# Cell_monitoring_and_balancing.net
KiCad netlist of a schematic drawn in Altium Designer
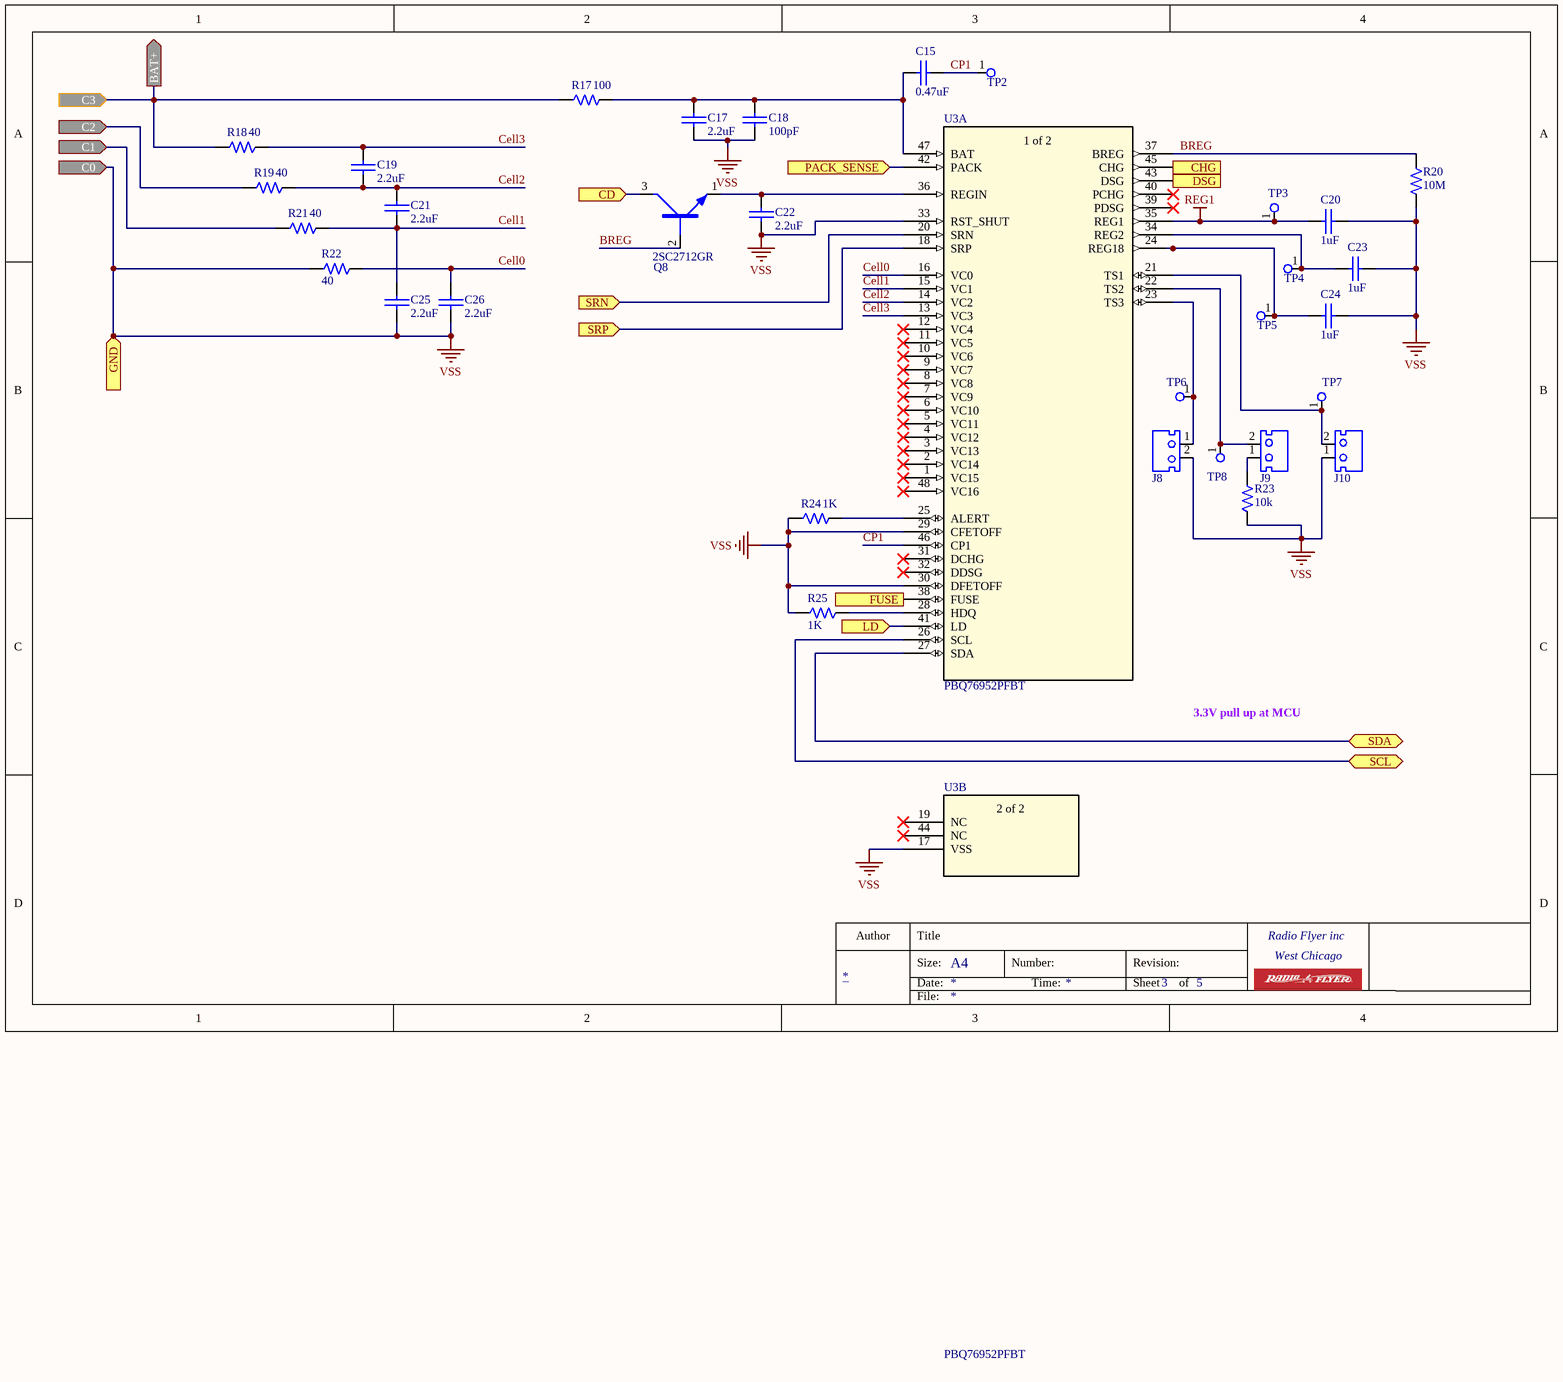
[diagram p0: Cell monitoring and balancing.SchDoc]

(export (version "E")
  (design (tool "Eeschema 10.0.6"))
  (components
    (comp (ref "C15")
      (value "0.47uF")
      (footprint "CAPC0603-RW")
      (description "CAP X7R .01UF 16V +-10% 0603 WALSIN L")
      (fields
        (field (name "MFG") "WALSIN")
        (field (name "TOLERANCE") "10%")
        (field (name "CREATE_NAME") "Nathan")
      )
      (libsource (lib "P-Capacitors") (part "CAP0603 0.01uF 16V 10%_X7R_WALSIN"))
    )
    (comp (ref "C17")
      (value "2.2uF")
      (footprint "CAPC0603-RW")
      (description "CAP X7R .01UF 16V +-10% 0603 WALSIN L")
      (fields
        (field (name "MFG") "WALSIN")
        (field (name "TOLERANCE") "10%")
        (field (name "CREATE_NAME") "Nathan")
      )
      (libsource (lib "P-Capacitors") (part "CAP0603 0.01uF 16V 10%_X7R_WALSIN"))
    )
    (comp (ref "C18")
      (value "100pF")
      (footprint "CAPC0603-RW")
      (description "CAP X7R .01UF 16V +-10% 0603 WALSIN L")
      (fields
        (field (name "MFG") "WALSIN")
        (field (name "TOLERANCE") "10%")
        (field (name "CREATE_NAME") "Nathan")
      )
      (libsource (lib "P-Capacitors") (part "CAP0603 0.01uF 16V 10%_X7R_WALSIN"))
    )
    (comp (ref "C19")
      (value "2.2uF")
      (footprint "CAPC0603-RW")
      (description "CAP X7R .01UF 16V +-10% 0603 WALSIN L")
      (fields
        (field (name "MFG") "WALSIN")
        (field (name "TOLERANCE") "10%")
        (field (name "CREATE_NAME") "Nathan")
      )
      (libsource (lib "P-Capacitors") (part "CAP0603 0.01uF 16V 10%_X7R_WALSIN"))
    )
    (comp (ref "C20")
      (value "1uF")
      (footprint "CAPC0603-RW")
      (description "CAP X7R .01UF 16V +-10% 0603 WALSIN L")
      (fields
        (field (name "MFG") "WALSIN")
        (field (name "TOLERANCE") "10%")
        (field (name "CREATE_NAME") "Nathan")
      )
      (libsource (lib "P-Capacitors") (part "CAP0603 0.01uF 16V 10%_X7R_WALSIN"))
    )
    (comp (ref "C21")
      (value "2.2uF")
      (footprint "CAPC0603-RW")
      (description "CAP X7R .01UF 16V +-10% 0603 WALSIN L")
      (fields
        (field (name "MFG") "WALSIN")
        (field (name "TOLERANCE") "10%")
        (field (name "CREATE_NAME") "Nathan")
      )
      (libsource (lib "P-Capacitors") (part "CAP0603 0.01uF 16V 10%_X7R_WALSIN"))
    )
    (comp (ref "C22")
      (value "2.2uF")
      (footprint "CAPC0603-RW")
      (description "CAP X7R .01UF 16V +-10% 0603 WALSIN L")
      (fields
        (field (name "MFG") "WALSIN")
        (field (name "TOLERANCE") "10%")
        (field (name "CREATE_NAME") "Nathan")
      )
      (libsource (lib "P-Capacitors") (part "CAP0603 0.01uF 16V 10%_X7R_WALSIN"))
    )
    (comp (ref "C23")
      (value "1uF")
      (footprint "CAPC0603-RW")
      (description "CAP X7R .01UF 16V +-10% 0603 WALSIN L")
      (fields
        (field (name "MFG") "WALSIN")
        (field (name "TOLERANCE") "10%")
        (field (name "CREATE_NAME") "Nathan")
      )
      (libsource (lib "P-Capacitors") (part "CAP0603 0.01uF 16V 10%_X7R_WALSIN"))
    )
    (comp (ref "C24")
      (value "1uF")
      (footprint "CAPC0603-RW")
      (description "CAP X7R .01UF 16V +-10% 0603 WALSIN L")
      (fields
        (field (name "MFG") "WALSIN")
        (field (name "TOLERANCE") "10%")
        (field (name "CREATE_NAME") "Nathan")
      )
      (libsource (lib "P-Capacitors") (part "CAP0603 0.01uF 16V 10%_X7R_WALSIN"))
    )
    (comp (ref "C25")
      (value "2.2uF")
      (footprint "CAPC0603-RW")
      (description "CAP X7R .01UF 16V +-10% 0603 WALSIN L")
      (fields
        (field (name "MFG") "WALSIN")
        (field (name "TOLERANCE") "10%")
        (field (name "CREATE_NAME") "Nathan")
      )
      (libsource (lib "P-Capacitors") (part "CAP0603 0.01uF 16V 10%_X7R_WALSIN"))
    )
    (comp (ref "C26")
      (value "2.2uF")
      (footprint "CAPC0603-RW")
      (description "CAP X7R .01UF 16V +-10% 0603 WALSIN L")
      (fields
        (field (name "MFG") "WALSIN")
        (field (name "TOLERANCE") "10%")
        (field (name "CREATE_NAME") "Nathan")
      )
      (libsource (lib "P-Capacitors") (part "CAP0603 0.01uF 16V 10%_X7R_WALSIN"))
    )
    (comp (ref "J8")
      (value "CCN250002-0102")
      (footprint "CONN 2P PH=2.5mm HAA250A-2 RED")
      (description "CONNECTOR HA2.5 2PIN RED G")
      (fields
        (field (name "MFG") "金瑞康")
        (field (name "MFG PART") "HAA250A-2 RED")
        (field (name "CREATE_NAME") "Nathan")
      )
      (libsource (lib "C-Connector") (part "CONN 2P PH=2.5mm HAA250A-2 RED"))
    )
    (comp (ref "J9")
      (value "CCN250002-0102")
      (footprint "CONN 2P PH=2.5mm HAA250A-2 RED")
      (description "CONNECTOR HA2.5 2PIN RED G")
      (fields
        (field (name "MFG") "金瑞康")
        (field (name "MFG PART") "HAA250A-2 RED")
        (field (name "CREATE_NAME") "Nathan")
      )
      (libsource (lib "") (part "CONN 2P PH=2.5mm HAA250A-2 RED_1"))
    )
    (comp (ref "J10")
      (value "CCN250002-0102")
      (footprint "CONN 2P PH=2.5mm HAA250A-2 RED")
      (description "CONNECTOR HA2.5 2PIN RED G")
      (fields
        (field (name "MFG") "金瑞康")
        (field (name "MFG PART") "HAA250A-2 RED")
        (field (name "CREATE_NAME") "Nathan")
      )
      (libsource (lib "") (part "CONN 2P PH=2.5mm HAA250A-2 RED_1"))
    )
    (comp (ref "Q8")
      (value "T5810040804A0")
      (footprint "2SC2712GR")
      (description "NPN 50V 2SC2712GR SOT23 BLUE R K")
      (fields
        (field (name "MFG") "BLUE ROCKET(藍箭電子)")
        (field (name "VOLTAGE") "50V")
        (field (name "MFG PART") "2SC2712GR")
        (field (name "CREATE_NAME") "Nathan")
      )
      (libsource (lib "R-Semiconductors") (part "2SC2712GR"))
    )
    (comp (ref "R17")
      (value "100")
      (footprint "0603-RW")
      (description "CHIP 976 OHM 100PPM +-1% 0603 WALS L")
      (fields (field (name "POWER") "0.1W") (field (name "MFG") "WALSIN") (field (name "CREATE_NAME") "Tom"))
      (libsource (lib "Q-Resistors") (part "RES0603 1/10W +-1% 976 OHM 100PPM"))
    )
    (comp (ref "R18")
      (value "40")
      (footprint "0603-RW")
      (description "CHIP 976 OHM 100PPM +-1% 0603 WALS L")
      (fields (field (name "POWER") "0.1W") (field (name "MFG") "WALSIN") (field (name "CREATE_NAME") "Tom"))
      (libsource (lib "Q-Resistors") (part "RES0603 1/10W +-1% 976 OHM 100PPM"))
    )
    (comp (ref "R19")
      (value "40")
      (footprint "0603-RW")
      (description "CHIP 976 OHM 100PPM +-1% 0603 WALS L")
      (fields (field (name "POWER") "0.1W") (field (name "MFG") "WALSIN") (field (name "CREATE_NAME") "Tom"))
      (libsource (lib "Q-Resistors") (part "RES0603 1/10W +-1% 976 OHM 100PPM"))
    )
    (comp (ref "R20")
      (value "10M")
      (footprint "0603-RW")
      (description "CHIP 976 OHM 100PPM +-1% 0603 WALS L")
      (fields (field (name "POWER") "0.1W") (field (name "MFG") "WALSIN") (field (name "CREATE_NAME") "Tom"))
      (libsource (lib "Q-Resistors") (part "RES0603 1/10W +-1% 976 OHM 100PPM"))
    )
    (comp (ref "R21")
      (value "40")
      (footprint "0603-RW")
      (description "CHIP 976 OHM 100PPM +-1% 0603 WALS L")
      (fields (field (name "POWER") "0.1W") (field (name "MFG") "WALSIN") (field (name "CREATE_NAME") "Tom"))
      (libsource (lib "Q-Resistors") (part "RES0603 1/10W +-1% 976 OHM 100PPM"))
    )
    (comp (ref "R22")
      (value "40")
      (footprint "0603-RW")
      (description "CHIP 976 OHM 100PPM +-1% 0603 WALS L")
      (fields (field (name "POWER") "0.1W") (field (name "MFG") "WALSIN") (field (name "CREATE_NAME") "Tom"))
      (libsource (lib "Q-Resistors") (part "RES0603 1/10W +-1% 976 OHM 100PPM"))
    )
    (comp (ref "R23")
      (value "10k")
      (footprint "0603-RW")
      (description "CHIP 976 OHM 100PPM +-1% 0603 WALS L")
      (fields (field (name "POWER") "0.1W") (field (name "MFG") "WALSIN") (field (name "CREATE_NAME") "Tom"))
      (libsource (lib "Q-Resistors") (part "RES0603 1/10W +-1% 976 OHM 100PPM"))
    )
    (comp (ref "R24")
      (value "1K")
      (footprint "0603-RW")
      (description "CHIP 976 OHM 100PPM +-1% 0603 WALS L")
      (fields (field (name "POWER") "0.1W") (field (name "MFG") "WALSIN") (field (name "CREATE_NAME") "Tom"))
      (libsource (lib "Q-Resistors") (part "RES0603 1/10W +-1% 976 OHM 100PPM"))
    )
    (comp (ref "R25")
      (value "1K")
      (footprint "0603-RW")
      (description "CHIP 976 OHM 100PPM +-1% 0603 WALS L")
      (fields (field (name "POWER") "0.1W") (field (name "MFG") "WALSIN") (field (name "CREATE_NAME") "Tom"))
      (libsource (lib "Q-Resistors") (part "RES0603 1/10W +-1% 976 OHM 100PPM"))
    )
    (comp (ref "TP2")
      (value "CP1")
      (footprint "RT-01T-1.0B")
      (description "TERMINAL 11MM G")
      (fields
        (field (name "MFG") "利民豐（JST)")
        (field (name "MFG PART") "RT-01T-1.0B")
        (field (name "CREATE_NAME") "Nathan")
      )
      (libsource (lib "C-Connector") (part "TERMINAL RT-01T-1.0B"))
    )
    (comp (ref "TP3")
      (value "CP1")
      (footprint "RT-01T-1.0B")
      (description "TERMINAL 11MM G")
      (fields
        (field (name "MFG") "利民豐（JST)")
        (field (name "MFG PART") "RT-01T-1.0B")
        (field (name "CREATE_NAME") "Nathan")
      )
      (libsource (lib "C-Connector") (part "TERMINAL RT-01T-1.0B"))
    )
    (comp (ref "TP4")
      (value "CP1")
      (footprint "RT-01T-1.0B")
      (description "TERMINAL 11MM G")
      (fields
        (field (name "MFG") "利民豐（JST)")
        (field (name "MFG PART") "RT-01T-1.0B")
        (field (name "CREATE_NAME") "Nathan")
      )
      (libsource (lib "C-Connector") (part "TERMINAL RT-01T-1.0B"))
    )
    (comp (ref "TP5")
      (value "CP1")
      (footprint "RT-01T-1.0B")
      (description "TERMINAL 11MM G")
      (fields
        (field (name "MFG") "利民豐（JST)")
        (field (name "MFG PART") "RT-01T-1.0B")
        (field (name "CREATE_NAME") "Nathan")
      )
      (libsource (lib "C-Connector") (part "TERMINAL RT-01T-1.0B"))
    )
    (comp (ref "TP6")
      (value "CP1")
      (footprint "RT-01T-1.0B")
      (description "TERMINAL 11MM G")
      (fields
        (field (name "MFG") "利民豐（JST)")
        (field (name "MFG PART") "RT-01T-1.0B")
        (field (name "CREATE_NAME") "Nathan")
      )
      (libsource (lib "C-Connector") (part "TERMINAL RT-01T-1.0B"))
    )
    (comp (ref "TP7")
      (value "CP1")
      (footprint "RT-01T-1.0B")
      (description "TERMINAL 11MM G")
      (fields
        (field (name "MFG") "利民豐（JST)")
        (field (name "MFG PART") "RT-01T-1.0B")
        (field (name "CREATE_NAME") "Nathan")
      )
      (libsource (lib "C-Connector") (part "TERMINAL RT-01T-1.0B"))
    )
    (comp (ref "TP8")
      (value "CP1")
      (footprint "RT-01T-1.0B")
      (description "TERMINAL 11MM G")
      (fields
        (field (name "MFG") "利民豐（JST)")
        (field (name "MFG PART") "RT-01T-1.0B")
        (field (name "CREATE_NAME") "Nathan")
      )
      (libsource (lib "C-Connector") (part "TERMINAL RT-01T-1.0B"))
    )
    (comp (ref "U3")
      (value "PBQ76952PFBT")
      (footprint "PFB48_TEX")
      (description "No Description Available")
      (libsource (lib "PBQ76952PFBT") (part "PBQ76952PFBT"))
    )
  )
  (nets
    (net (code "1") (name "/BAT+") (class "Default")
      (node (ref "R17") (pin "1") (pinfunction "1_1") (pintype "passive"))
      (node (ref "R18") (pin "1") (pinfunction "1_1") (pintype "passive"))
    )
    (net (code "2") (name "/BREG") (class "Default")
      (node (ref "Q8") (pin "2") (pinfunction "B_2") (pintype "passive"))
      (node (ref "R20") (pin "1") (pinfunction "1_1") (pintype "passive"))
      (node (ref "U3") (pin "37") (pinfunction "BREG_37") (pintype "output"))
    )
    (net (code "3") (name "/C1") (class "Default")
      (node (ref "R21") (pin "1") (pinfunction "1_1") (pintype "passive"))
    )
    (net (code "4") (name "/C2") (class "Default")
      (node (ref "R19") (pin "1") (pinfunction "1_1") (pintype "passive"))
    )
    (net (code "5") (name "/CD") (class "Default")
      (node (ref "Q8") (pin "3") (pinfunction "C_3") (pintype "passive"))
    )
    (net (code "6") (name "/CHG") (class "Default")
      (node (ref "U3") (pin "45") (pinfunction "CHG_45") (pintype "output"))
    )
    (net (code "7") (name "/CP1") (class "Default")
      (node (ref "C15") (pin "1") (pinfunction "1_1") (pintype "passive"))
      (node (ref "TP2") (pin "1") (pinfunction "1_1") (pintype "passive"))
      (node (ref "U3") (pin "46") (pinfunction "CP1_46") (pintype "bidirectional"))
    )
    (net (code "8") (name "/Cell0") (class "Default")
      (node (ref "C26") (pin "2") (pinfunction "2_2") (pintype "passive"))
      (node (ref "R22") (pin "2") (pinfunction "2_2") (pintype "passive"))
      (node (ref "U3") (pin "16") (pinfunction "VC0_16") (pintype "input"))
    )
    (net (code "9") (name "/Cell1") (class "Default")
      (node (ref "C21") (pin "1") (pinfunction "1_1") (pintype "passive"))
      (node (ref "C25") (pin "2") (pinfunction "2_2") (pintype "passive"))
      (node (ref "R21") (pin "2") (pinfunction "2_2") (pintype "passive"))
      (node (ref "U3") (pin "15") (pinfunction "VC1_15") (pintype "input"))
    )
    (net (code "10") (name "/Cell2") (class "Default")
      (node (ref "C19") (pin "1") (pinfunction "1_1") (pintype "passive"))
      (node (ref "C21") (pin "2") (pinfunction "2_2") (pintype "passive"))
      (node (ref "R19") (pin "2") (pinfunction "2_2") (pintype "passive"))
      (node (ref "U3") (pin "14") (pinfunction "VC2_14") (pintype "input"))
    )
    (net (code "11") (name "/Cell3") (class "Default")
      (node (ref "C19") (pin "2") (pinfunction "2_2") (pintype "passive"))
      (node (ref "R18") (pin "2") (pinfunction "2_2") (pintype "passive"))
      (node (ref "U3") (pin "13") (pinfunction "VC3_13") (pintype "input"))
    )
    (net (code "12") (name "/DSG") (class "Default")
      (node (ref "U3") (pin "43") (pinfunction "DSG_43") (pintype "output"))
    )
    (net (code "13") (name "/FUSE") (class "Default")
      (node (ref "U3") (pin "38") (pinfunction "FUSE_38") (pintype "bidirectional"))
    )
    (net (code "14") (name "/LD") (class "Default")
      (node (ref "U3") (pin "41") (pinfunction "LD_41") (pintype "bidirectional"))
    )
    (net (code "15") (name "/PACK_SENSE") (class "Default")
      (node (ref "U3") (pin "42") (pinfunction "PACK_42") (pintype "input"))
    )
    (net (code "16") (name "/SCL") (class "Default")
      (node (ref "U3") (pin "26") (pinfunction "SCL_26") (pintype "bidirectional"))
    )
    (net (code "17") (name "/SDA") (class "Default")
      (node (ref "U3") (pin "27") (pinfunction "SDA_27") (pintype "bidirectional"))
    )
    (net (code "18") (name "/SRN") (class "Default")
      (node (ref "U3") (pin "20") (pinfunction "SRN_20") (pintype "input"))
    )
    (net (code "19") (name "/SRP") (class "Default")
      (node (ref "U3") (pin "18") (pinfunction "SRP_18") (pintype "input"))
    )
    (net (code "20") (name "Net-(J9-Pad1)") (class "Default")
      (node (ref "J9") (pin "1") (pinfunction "1_1") (pintype "passive"))
      (node (ref "R23") (pin "1") (pinfunction "1_1") (pintype "passive"))
    )
    (net (code "21") (name "Net-(Q8-E)") (class "Default")
      (node (ref "C22") (pin "2") (pinfunction "2_2") (pintype "passive"))
      (node (ref "Q8") (pin "1") (pinfunction "E_1") (pintype "passive"))
      (node (ref "U3") (pin "36") (pinfunction "REGIN_36") (pintype "input"))
    )
    (net (code "22") (name "Net-(U3A-ALERT)") (class "Default")
      (node (ref "R24") (pin "2") (pinfunction "2_2") (pintype "passive"))
      (node (ref "U3") (pin "25") (pinfunction "ALERT_25") (pintype "bidirectional"))
    )
    (net (code "23") (name "Net-(U3A-BAT)") (class "Default")
      (node (ref "C15") (pin "2") (pinfunction "2_2") (pintype "passive"))
      (node (ref "C17") (pin "2") (pinfunction "2_2") (pintype "passive"))
      (node (ref "C18") (pin "2") (pinfunction "2_2") (pintype "passive"))
      (node (ref "R17") (pin "2") (pinfunction "2_2") (pintype "passive"))
      (node (ref "U3") (pin "47") (pinfunction "BAT_47") (pintype "input"))
    )
    (net (code "24") (name "Net-(U3A-HDQ)") (class "Default")
      (node (ref "R25") (pin "2") (pinfunction "2_2") (pintype "passive"))
      (node (ref "U3") (pin "28") (pinfunction "HDQ_28") (pintype "bidirectional"))
    )
    (net (code "25") (name "Net-(U3A-REG2)") (class "Default")
      (node (ref "C23") (pin "2") (pinfunction "2_2") (pintype "passive"))
      (node (ref "TP4") (pin "1") (pinfunction "1_1") (pintype "passive"))
      (node (ref "U3") (pin "34") (pinfunction "REG2_34") (pintype "output"))
    )
    (net (code "26") (name "Net-(U3A-REG18)") (class "Default")
      (node (ref "C24") (pin "2") (pinfunction "2_2") (pintype "passive"))
      (node (ref "TP5") (pin "1") (pinfunction "1_1") (pintype "passive"))
      (node (ref "U3") (pin "24") (pinfunction "REG18_24") (pintype "output"))
    )
    (net (code "27") (name "Net-(U3A-TS1)") (class "Default")
      (node (ref "J10") (pin "2") (pinfunction "2_2") (pintype "passive"))
      (node (ref "TP7") (pin "1") (pinfunction "1_1") (pintype "passive"))
      (node (ref "U3") (pin "21") (pinfunction "TS1_21") (pintype "bidirectional"))
    )
    (net (code "28") (name "Net-(U3A-TS2)") (class "Default")
      (node (ref "J9") (pin "2") (pinfunction "2_2") (pintype "passive"))
      (node (ref "TP8") (pin "1") (pinfunction "1_1") (pintype "passive"))
      (node (ref "U3") (pin "22") (pinfunction "TS2_22") (pintype "bidirectional"))
    )
    (net (code "29") (name "Net-(U3A-TS3)") (class "Default")
      (node (ref "J8") (pin "1") (pinfunction "1_1") (pintype "passive"))
      (node (ref "TP6") (pin "1") (pinfunction "1_1") (pintype "passive"))
      (node (ref "U3") (pin "23") (pinfunction "TS3_23") (pintype "bidirectional"))
    )
    (net (code "30") (name "REG1") (class "Default")
      (node (ref "C20") (pin "2") (pinfunction "2_2") (pintype "passive"))
      (node (ref "TP3") (pin "1") (pinfunction "1_1") (pintype "passive"))
      (node (ref "U3") (pin "35") (pinfunction "REG1_35") (pintype "output"))
    )
    (net (code "31") (name "VSS") (class "Default")
      (node (ref "C17") (pin "1") (pinfunction "1_1") (pintype "passive"))
      (node (ref "C18") (pin "1") (pinfunction "1_1") (pintype "passive"))
      (node (ref "C20") (pin "1") (pinfunction "1_1") (pintype "passive"))
      (node (ref "C22") (pin "1") (pinfunction "1_1") (pintype "passive"))
      (node (ref "C23") (pin "1") (pinfunction "1_1") (pintype "passive"))
      (node (ref "C24") (pin "1") (pinfunction "1_1") (pintype "passive"))
      (node (ref "C25") (pin "1") (pinfunction "1_1") (pintype "passive"))
      (node (ref "C26") (pin "1") (pinfunction "1_1") (pintype "passive"))
      (node (ref "J10") (pin "1") (pinfunction "1_1") (pintype "passive"))
      (node (ref "J8") (pin "2") (pinfunction "2_2") (pintype "passive"))
      (node (ref "R20") (pin "2") (pinfunction "2_2") (pintype "passive"))
      (node (ref "R22") (pin "1") (pinfunction "1_1") (pintype "passive"))
      (node (ref "R23") (pin "2") (pinfunction "2_2") (pintype "passive"))
      (node (ref "R24") (pin "1") (pinfunction "1_1") (pintype "passive"))
      (node (ref "R25") (pin "1") (pinfunction "1_1") (pintype "passive"))
      (node (ref "U3") (pin "17") (pinfunction "VSS_17") (pintype "power_in"))
      (node (ref "U3") (pin "29") (pinfunction "CFETOFF_29") (pintype "bidirectional"))
      (node (ref "U3") (pin "30") (pinfunction "DFETOFF_30") (pintype "bidirectional"))
      (node (ref "U3") (pin "33") (pinfunction "RST_SHUT_33") (pintype "input"))
    )
    (net (code "32") (name "unconnected-(U3A-DCHG-Pad31)") (class "Default")
      (node (ref "U3") (pin "31") (pinfunction "DCHG_31") (pintype "bidirectional+no_connect"))
    )
    (net (code "33") (name "unconnected-(U3A-DDSG-Pad32)") (class "Default")
      (node (ref "U3") (pin "32") (pinfunction "DDSG_32") (pintype "bidirectional+no_connect"))
    )
    (net (code "34") (name "unconnected-(U3A-PCHG-Pad40)") (class "Default")
      (node (ref "U3") (pin "40") (pinfunction "PCHG_40") (pintype "output+no_connect"))
    )
    (net (code "35") (name "unconnected-(U3A-PDSG-Pad39)") (class "Default")
      (node (ref "U3") (pin "39") (pinfunction "PDSG_39") (pintype "output+no_connect"))
    )
    (net (code "36") (name "unconnected-(U3A-VC4-Pad12)") (class "Default")
      (node (ref "U3") (pin "12") (pinfunction "VC4_12") (pintype "input+no_connect"))
    )
    (net (code "37") (name "unconnected-(U3A-VC5-Pad11)") (class "Default")
      (node (ref "U3") (pin "11") (pinfunction "VC5_11") (pintype "input+no_connect"))
    )
    (net (code "38") (name "unconnected-(U3A-VC6-Pad10)") (class "Default")
      (node (ref "U3") (pin "10") (pinfunction "VC6_10") (pintype "input+no_connect"))
    )
    (net (code "39") (name "unconnected-(U3A-VC7-Pad9)") (class "Default")
      (node (ref "U3") (pin "9") (pinfunction "VC7_9") (pintype "input+no_connect"))
    )
    (net (code "40") (name "unconnected-(U3A-VC8-Pad8)") (class "Default")
      (node (ref "U3") (pin "8") (pinfunction "VC8_8") (pintype "input+no_connect"))
    )
    (net (code "41") (name "unconnected-(U3A-VC9-Pad7)") (class "Default")
      (node (ref "U3") (pin "7") (pinfunction "VC9_7") (pintype "input+no_connect"))
    )
    (net (code "42") (name "unconnected-(U3A-VC10-Pad6)") (class "Default")
      (node (ref "U3") (pin "6") (pinfunction "VC10_6") (pintype "input+no_connect"))
    )
    (net (code "43") (name "unconnected-(U3A-VC11-Pad5)") (class "Default")
      (node (ref "U3") (pin "5") (pinfunction "VC11_5") (pintype "input+no_connect"))
    )
    (net (code "44") (name "unconnected-(U3A-VC12-Pad4)") (class "Default")
      (node (ref "U3") (pin "4") (pinfunction "VC12_4") (pintype "input+no_connect"))
    )
    (net (code "45") (name "unconnected-(U3A-VC13-Pad3)") (class "Default")
      (node (ref "U3") (pin "3") (pinfunction "VC13_3") (pintype "input+no_connect"))
    )
    (net (code "46") (name "unconnected-(U3A-VC14-Pad2)") (class "Default")
      (node (ref "U3") (pin "2") (pinfunction "VC14_2") (pintype "input+no_connect"))
    )
    (net (code "47") (name "unconnected-(U3A-VC15-Pad1)") (class "Default")
      (node (ref "U3") (pin "1") (pinfunction "VC15_1") (pintype "input+no_connect"))
    )
    (net (code "48") (name "unconnected-(U3A-VC16-Pad48)") (class "Default")
      (node (ref "U3") (pin "48") (pinfunction "VC16_48") (pintype "input+no_connect"))
    )
    (net (code "49") (name "unconnected-(U3B-NC-Pad19)") (class "Default")
      (node (ref "U3") (pin "19") (pinfunction "NC_19") (pintype "passive+no_connect"))
    )
    (net (code "50") (name "unconnected-(U3B-NC-Pad44)") (class "Default")
      (node (ref "U3") (pin "44") (pinfunction "NC_44") (pintype "passive+no_connect"))
    )
  )
)
